# BMS.net
KiCad netlist of a schematic drawn in Altium Designer
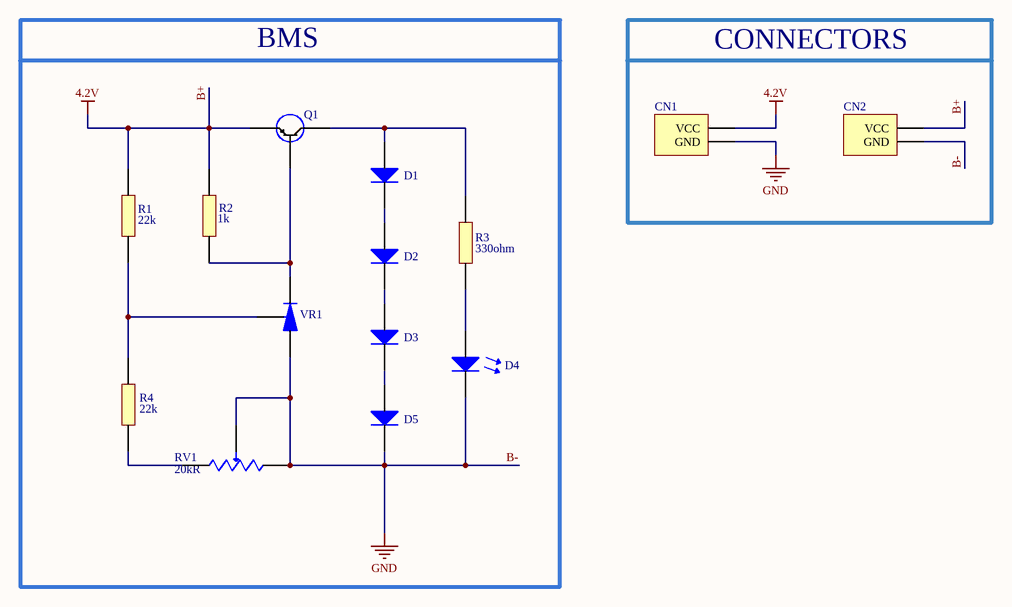
[diagram p0: BMS.SchDoc]

(export (version "E")
  (design (tool "Eeschema 10.0.6"))
  (components
    (comp (ref "CN1")
      (value "TB002-500-02BE")
      (footprint "CONNECTOR_2PIN")
      (description "2~24 Poles, Screw Type, Horizontal, 5.0 Pitch, 22~12 (AWG), Terminal Block Connector")
      (fields (field (name "MANUFACTURER") "CUI") (field (name "DESIGNEDBY") "Nasıf Can Peltek"))
      (libsource (lib "BMS_Library") (part "CONNECTOR"))
    )
    (comp (ref "CN2")
      (value "TB002-500-02BE")
      (footprint "CONNECTOR_2PIN")
      (description "2~24 Poles, Screw Type, Horizontal, 5.0 Pitch, 22~12 (AWG), Terminal Block Connector")
      (fields (field (name "MANUFACTURER") "CUI") (field (name "DESIGNEDBY") "Nasıf Can Peltek"))
      (libsource (lib "BMS_Library") (part "CONNECTOR"))
    )
    (comp (ref "D1")
      (value "4878-1N4007TR-ND")
      (footprint "1N4007")
      (description "Rectifier Diode, 1 Phase, 1 Element, 1A, 1000V V(RRM), Silicon, DO-41")
      (fields
        (field (name "MANUFACTURER") "Diotec")
        (field (name "MANUFACTURER PART NUMBER") "1N4007")
        (field (name "DESIGNEDBY") "Nasıf Can Peltek")
      )
      (libsource (lib "BMS_Library") (part "DIODE1N4007"))
    )
    (comp (ref "D2")
      (value "4878-1N4007TR-ND")
      (footprint "1N4007")
      (description "Rectifier Diode, 1 Phase, 1 Element, 1A, 1000V V(RRM), Silicon, DO-41")
      (fields
        (field (name "MANUFACTURER") "Diotec")
        (field (name "MANUFACTURER PART NUMBER") "1N4007")
        (field (name "DESIGNEDBY") "Nasıf Can Peltek")
      )
      (libsource (lib "BMS_Library") (part "DIODE1N4007"))
    )
    (comp (ref "D3")
      (value "4878-1N4007TR-ND")
      (footprint "1N4007")
      (description "Rectifier Diode, 1 Phase, 1 Element, 1A, 1000V V(RRM), Silicon, DO-41")
      (fields
        (field (name "MANUFACTURER") "Diotec")
        (field (name "MANUFACTURER PART NUMBER") "1N4007")
        (field (name "DESIGNEDBY") "Nasıf Can Peltek")
      )
      (libsource (lib "BMS_Library") (part "DIODE1N4007"))
    )
    (comp (ref "D4")
      (value "C503B-GAN-CB0F0791")
      (footprint "LED")
      (description "Round 503-B Series Led -green Color, Full Rank, Bulk Pack")
      (fields (field (name "MANUFACTURER") "Cree") (field (name "DESIGNEDBY") "Nasıf Can Peltek"))
      (libsource (lib "BMS_Library") (part "5MM_LED_RED"))
    )
    (comp (ref "D5")
      (value "4878-1N4007TR-ND")
      (footprint "1N4007")
      (description "Rectifier Diode, 1 Phase, 1 Element, 1A, 1000V V(RRM), Silicon, DO-41")
      (fields
        (field (name "MANUFACTURER") "Diotec")
        (field (name "MANUFACTURER PART NUMBER") "1N4007")
        (field (name "DESIGNEDBY") "Nasıf Can Peltek")
      )
      (libsource (lib "BMS_Library") (part "DIODE1N4007"))
    )
    (comp (ref "Q1")
      (value "BD140OS-ND Transistör BJT TO126 - PNP 80V 1.5A")
      (footprint "TO126")
      (description "1.5 A, 80 V PNP Bipolar Power Transistor")
      (fields
        (field (name "MANUFACTURER") "ON Semiconductor")
        (field (name "MANUFACTURER PART NUMBER") "BD140G")
        (field (name "DESIGNEDBY") "Nasıf Can Peltek")
      )
      (libsource (lib "BMS_Library") (part "BD140"))
    )
    (comp (ref "R1")
      (value "CF14JT22K0")
      (footprint "RESISTOR")
      (description "Res Carbon Film 22K Ohm 5% 1/4W -500ppm/°C to 0ppm/°C Conformal AXL Thru-Hole T/R")
      (fields
        (field (name "MANUFACTURER") "Stackpole Electronics")
        (field (name "RESISTANCE") "22k")
        (field (name "DESIGNEDBY") "Nasıf Can Peltek")
      )
      (libsource (lib "BMS_Library") (part "22K_RESISTOR"))
    )
    (comp (ref "R2")
      (value "CF14JT1K00")
      (footprint "RESISTOR")
      (description "Res Carbon Film 1K Ohm 5% 1/4W -400ppm/°C to 0ppm/°C Conformal AXL Thru-Hole T/R")
      (fields
        (field (name "MANUFACTURER") "Stackpole Electronics")
        (field (name "RESISTANCE") "1k")
        (field (name "DESIGNEDBY") "Nasıf Can Peltek")
      )
      (libsource (lib "BMS_Library") (part "1K_RESISTOR"))
    )
    (comp (ref "R3")
      (value "CF14JT330R")
      (footprint "RESISTOR")
      (description "Res Carbon Film 330 Ohm 5% 1/4W -400ppm/°C to 0ppm/°C Conformal AXL Thru-Hole T/R")
      (fields
        (field (name "MANUFACTURER") "Stackpole Electronics")
        (field (name "RESISTANCE") "330ohm")
        (field (name "DESIGNEDBY") "Nasıf Can Peltek")
      )
      (libsource (lib "BMS_Library") (part "330OHM_RESISTOR"))
    )
    (comp (ref "R4")
      (value "CF14JT22K0")
      (footprint "RESISTOR")
      (description "Res Carbon Film 22K Ohm 5% 1/4W -500ppm/°C to 0ppm/°C Conformal AXL Thru-Hole T/R")
      (fields
        (field (name "MANUFACTURER") "Stackpole Electronics")
        (field (name "RESISTANCE") "22k")
        (field (name "DESIGNEDBY") "Nasıf Can Peltek")
      )
      (libsource (lib "BMS_Library") (part "22K_RESISTOR"))
    )
    (comp (ref "RV1")
      (value "3296W-1-203LF")
      (footprint "3296")
      (description "Cermet Not Linear TRIMMER Trimmer Potentiometer 卤10% 500mW 70C 300V")
      (fields
        (field (name "MANUFACTURER") "Bourns")
        (field (name "TOLERANCE") "10%")
        (field (name "RESISTANCE") "20kR")
        (field (name "DESIGNEDBY") "Nasıf Can Peltek")
      )
      (libsource (lib "BMS_Library") (part "20K_TRIMPOT"))
    )
    (comp (ref "VR1")
      (value "TL431")
      (footprint "TO92")
      (description "V-Ref Adjustable 2.495V to 36V 100mA 3-Pin TO-92 Ammo")
      (fields
        (field (name "MANUFACTURER") "STMicroelectronics")
        (field (name "MANUFACTURER PART NUMBER") "TL431CZ-AP")
        (field (name "DESIGNEDBY") "Nasıf Can PELTEK")
      )
      (libsource (lib "BMS_Library") (part "TL431"))
    )
  )
  (nets
    (net (code "1") (name "4.2V") (class "Default")
      (node (ref "CN1") (pin "1") (pinfunction "VCC_1") (pintype "passive"))
      (node (ref "CN2") (pin "1") (pinfunction "VCC_1") (pintype "passive"))
      (node (ref "Q1") (pin "3") (pinfunction "Emitter_3") (pintype "passive"))
      (node (ref "R1") (pin "2") (pinfunction "2_2") (pintype "passive"))
      (node (ref "R2") (pin "2") (pinfunction "2_2") (pintype "passive"))
    )
    (net (code "2") (name "GND") (class "Default")
      (node (ref "CN1") (pin "2") (pinfunction "GND_2") (pintype "passive"))
      (node (ref "CN2") (pin "2") (pinfunction "GND_2") (pintype "passive"))
      (node (ref "D4") (pin "2") (pinfunction "2_2") (pintype "passive"))
      (node (ref "D5") (pin "2") (pinfunction "2_2") (pintype "passive"))
      (node (ref "RV1") (pin "2") (pinfunction "2_2") (pintype "passive"))
      (node (ref "RV1") (pin "3") (pinfunction "3_3") (pintype "passive"))
      (node (ref "VR1") (pin "2") (pinfunction "Anode(+)_2") (pintype "passive"))
    )
    (net (code "3") (name "Net-(D1-Pad2)") (class "Default")
      (node (ref "D1") (pin "2") (pinfunction "2_2") (pintype "passive"))
      (node (ref "D2") (pin "1") (pinfunction "1_1") (pintype "passive"))
    )
    (net (code "4") (name "Net-(D2-Pad2)") (class "Default")
      (node (ref "D2") (pin "2") (pinfunction "2_2") (pintype "passive"))
      (node (ref "D3") (pin "1") (pinfunction "1_1") (pintype "passive"))
    )
    (net (code "5") (name "Net-(D3-Pad2)") (class "Default")
      (node (ref "D3") (pin "2") (pinfunction "2_2") (pintype "passive"))
      (node (ref "D5") (pin "1") (pinfunction "1_1") (pintype "passive"))
    )
    (net (code "6") (name "Net-(D4-Pad1)") (class "Default")
      (node (ref "D4") (pin "1") (pinfunction "1_1") (pintype "passive"))
      (node (ref "R3") (pin "1") (pinfunction "1_1") (pintype "passive"))
    )
    (net (code "7") (name "Net-(Q1-Base)") (class "Default")
      (node (ref "Q1") (pin "1") (pinfunction "Base_1") (pintype "passive"))
      (node (ref "R2") (pin "1") (pinfunction "1_1") (pintype "passive"))
      (node (ref "VR1") (pin "1") (pinfunction "Cathode(-)_1") (pintype "passive"))
    )
    (net (code "8") (name "Net-(Q1-Collector)") (class "Default")
      (node (ref "D1") (pin "1") (pinfunction "1_1") (pintype "passive"))
      (node (ref "Q1") (pin "2") (pinfunction "Collector_2") (pintype "passive"))
      (node (ref "R3") (pin "2") (pinfunction "2_2") (pintype "passive"))
    )
    (net (code "9") (name "Net-(R4-Pad1)") (class "Default")
      (node (ref "R4") (pin "1") (pinfunction "1_1") (pintype "passive"))
      (node (ref "RV1") (pin "1") (pinfunction "1_1") (pintype "passive"))
    )
    (net (code "10") (name "Net-(VR1-Ref)") (class "Default")
      (node (ref "R1") (pin "1") (pinfunction "1_1") (pintype "passive"))
      (node (ref "R4") (pin "2") (pinfunction "2_2") (pintype "passive"))
      (node (ref "VR1") (pin "3") (pinfunction "Ref_3") (pintype "passive"))
    )
  )
)
